# BLE113.net
KiCad netlist of a schematic drawn in EAGLE
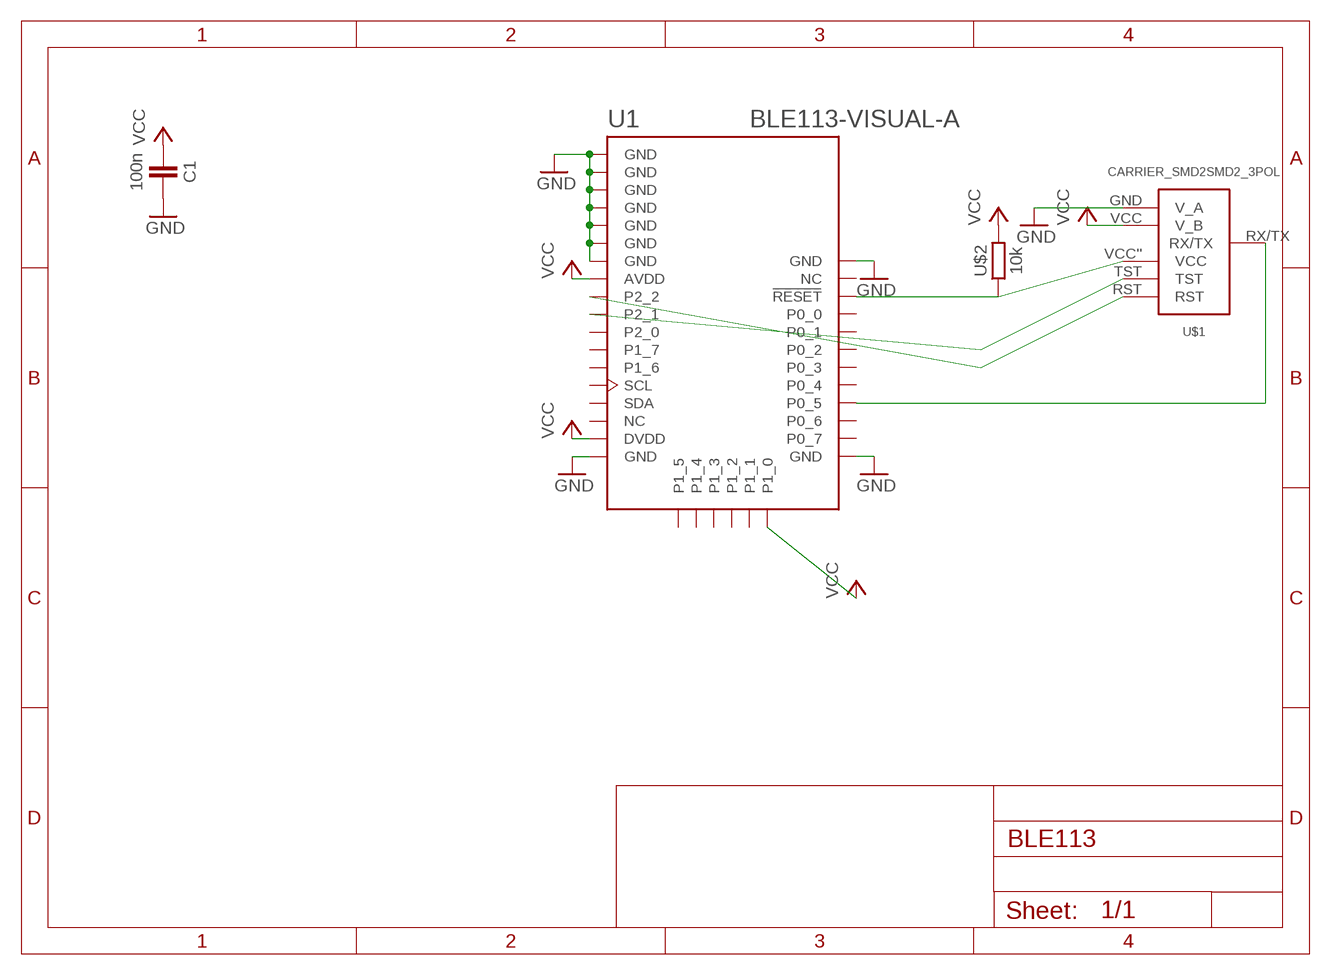
[diagram p0: schematic, sheet 1]

(export (version "E")
  (design (tool "Eeschema 10.0.6"))
  (components
    (comp (ref "C1")
      (value "100n")
      (footprint "eagle-import:603")
      (libsource (lib "eagle-import") (part "CAPACITOR"))
    )
    (comp (ref "U$1")
      (value "CARRIER_SMD2SMD2_3POL")
      (footprint "eagle-import:CARRIER_SMD2_3POL")
      (libsource (lib "eagle-import") (part "CARRIER_SMD2SMD2_3POL"))
    )
    (comp (ref "U$2")
      (value "10k")
      (footprint "eagle-import:603")
      (libsource (lib "eagle-import") (part "RESISTOR0603"))
    )
    (comp (ref "U1")
      (value "BLE113-VISUAL-A")
      (footprint "eagle-import:BLE113-A")
      (libsource (lib "eagle-import") (part "BLE113-VISUAL-A"))
    )
  )
  (nets
    (net (code "1") (name "GND") (class "Default")
      (node (ref "C1") (pin "2") (pinfunction "2_2") (pintype "passive"))
      (node (ref "U$1") (pin "GND") (pinfunction "V_A_GND") (pintype "bidirectional"))
      (node (ref "U1") (pin "GND") (pinfunction "GND_GND") (pintype "power_in"))
      (node (ref "U1") (pin "GND@10") (pinfunction "GND_GND@10") (pintype "power_in"))
      (node (ref "U1") (pin "GND@2") (pinfunction "GND_GND@2") (pintype "power_in"))
      (node (ref "U1") (pin "GND@3") (pinfunction "GND_GND@3") (pintype "power_in"))
      (node (ref "U1") (pin "GND@4") (pinfunction "GND_GND@4") (pintype "power_in"))
      (node (ref "U1") (pin "GND@5") (pinfunction "GND_GND@5") (pintype "power_in"))
      (node (ref "U1") (pin "GND@6") (pinfunction "GND_GND@6") (pintype "power_in"))
      (node (ref "U1") (pin "GND@7") (pinfunction "GND_GND@7") (pintype "power_in"))
      (node (ref "U1") (pin "GND@8") (pinfunction "GND_GND@8") (pintype "power_in"))
      (node (ref "U1") (pin "GND@9") (pinfunction "GND_GND@9") (pintype "power_in"))
    )
    (net (code "2") (name "Net-(U$1-PadRST)") (class "Default")
      (node (ref "U$1") (pin "RST") (pinfunction "RST_RST") (pintype "bidirectional"))
      (node (ref "U1") (pin "P2_2") (pinfunction "P2_2_P2_2") (pintype "bidirectional"))
    )
    (net (code "3") (name "Net-(U$1-PadRX{slash}TX)") (class "Default")
      (node (ref "U$1") (pin "RX/TX") (pinfunction "RX/TX_RX/TX") (pintype "bidirectional"))
      (node (ref "U1") (pin "P0_5") (pinfunction "P0_5_P0_5") (pintype "bidirectional"))
    )
    (net (code "4") (name "Net-(U$1-PadTST)") (class "Default")
      (node (ref "U$1") (pin "TST") (pinfunction "TST_TST") (pintype "bidirectional"))
      (node (ref "U1") (pin "P2_1") (pinfunction "P2_1_P2_1") (pintype "bidirectional"))
    )
    (net (code "5") (name "Net-(U$1-VCC)") (class "Default")
      (node (ref "U$1") (pin "VCC''") (pinfunction "VCC_VCC''") (pintype "bidirectional"))
      (node (ref "U$2") (pin "1") (pinfunction "1_1") (pintype "passive"))
      (node (ref "U1") (pin "RESET") (pinfunction "RESET_RESET") (pintype "input"))
    )
    (net (code "6") (name "VCC") (class "Default")
      (node (ref "C1") (pin "1") (pinfunction "1_1") (pintype "passive"))
      (node (ref "U$1") (pin "VCC") (pinfunction "V_B_VCC") (pintype "bidirectional"))
      (node (ref "U$2") (pin "2") (pinfunction "2_2") (pintype "passive"))
      (node (ref "U1") (pin "AVDD") (pinfunction "AVDD_AVDD") (pintype "power_in"))
      (node (ref "U1") (pin "DVDD") (pinfunction "DVDD_DVDD") (pintype "power_in"))
      (node (ref "U1") (pin "P1_0") (pinfunction "P1_0_P1_0") (pintype "bidirectional"))
    )
    (net (code "7") (name "unconnected-(U1-NC-PadNC@2)") (class "Default")
      (node (ref "U1") (pin "NC@2") (pinfunction "NC_NC@2") (pintype "no_connect"))
    )
    (net (code "8") (name "unconnected-(U1-PadNC)") (class "Default")
      (node (ref "U1") (pin "NC") (pinfunction "NC_NC") (pintype "no_connect"))
    )
    (net (code "9") (name "unconnected-(U1-PadP0_0)") (class "Default")
      (node (ref "U1") (pin "P0_0") (pinfunction "P0_0_P0_0") (pintype "bidirectional"))
    )
    (net (code "10") (name "unconnected-(U1-PadP0_1)") (class "Default")
      (node (ref "U1") (pin "P0_1") (pinfunction "P0_1_P0_1") (pintype "bidirectional"))
    )
    (net (code "11") (name "unconnected-(U1-PadP0_2)") (class "Default")
      (node (ref "U1") (pin "P0_2") (pinfunction "P0_2_P0_2") (pintype "bidirectional"))
    )
    (net (code "12") (name "unconnected-(U1-PadP0_3)") (class "Default")
      (node (ref "U1") (pin "P0_3") (pinfunction "P0_3_P0_3") (pintype "bidirectional"))
    )
    (net (code "13") (name "unconnected-(U1-PadP0_4)") (class "Default")
      (node (ref "U1") (pin "P0_4") (pinfunction "P0_4_P0_4") (pintype "bidirectional"))
    )
    (net (code "14") (name "unconnected-(U1-PadP0_6)") (class "Default")
      (node (ref "U1") (pin "P0_6") (pinfunction "P0_6_P0_6") (pintype "bidirectional"))
    )
    (net (code "15") (name "unconnected-(U1-PadP0_7)") (class "Default")
      (node (ref "U1") (pin "P0_7") (pinfunction "P0_7_P0_7") (pintype "bidirectional"))
    )
    (net (code "16") (name "unconnected-(U1-PadP1_1)") (class "Default")
      (node (ref "U1") (pin "P1_1") (pinfunction "P1_1_P1_1") (pintype "bidirectional"))
    )
    (net (code "17") (name "unconnected-(U1-PadP1_2)") (class "Default")
      (node (ref "U1") (pin "P1_2") (pinfunction "P1_2_P1_2") (pintype "bidirectional"))
    )
    (net (code "18") (name "unconnected-(U1-PadP1_3)") (class "Default")
      (node (ref "U1") (pin "P1_3") (pinfunction "P1_3_P1_3") (pintype "bidirectional"))
    )
    (net (code "19") (name "unconnected-(U1-PadP1_4)") (class "Default")
      (node (ref "U1") (pin "P1_4") (pinfunction "P1_4_P1_4") (pintype "bidirectional"))
    )
    (net (code "20") (name "unconnected-(U1-PadP1_5)") (class "Default")
      (node (ref "U1") (pin "P1_5") (pinfunction "P1_5_P1_5") (pintype "bidirectional"))
    )
    (net (code "21") (name "unconnected-(U1-PadP1_6)") (class "Default")
      (node (ref "U1") (pin "P1_6") (pinfunction "P1_6_P1_6") (pintype "bidirectional"))
    )
    (net (code "22") (name "unconnected-(U1-PadP1_7)") (class "Default")
      (node (ref "U1") (pin "P1_7") (pinfunction "P1_7_P1_7") (pintype "bidirectional"))
    )
    (net (code "23") (name "unconnected-(U1-PadP2_0)") (class "Default")
      (node (ref "U1") (pin "P2_0") (pinfunction "P2_0_P2_0") (pintype "bidirectional"))
    )
    (net (code "24") (name "unconnected-(U1-PadSCL)") (class "Default")
      (node (ref "U1") (pin "SCL") (pinfunction "SCL_SCL") (pintype "bidirectional"))
    )
    (net (code "25") (name "unconnected-(U1-PadSDA)") (class "Default")
      (node (ref "U1") (pin "SDA") (pinfunction "SDA_SDA") (pintype "bidirectional"))
    )
  )
)
